# Interfaces.net
KiCad netlist of a schematic drawn in Altium Designer
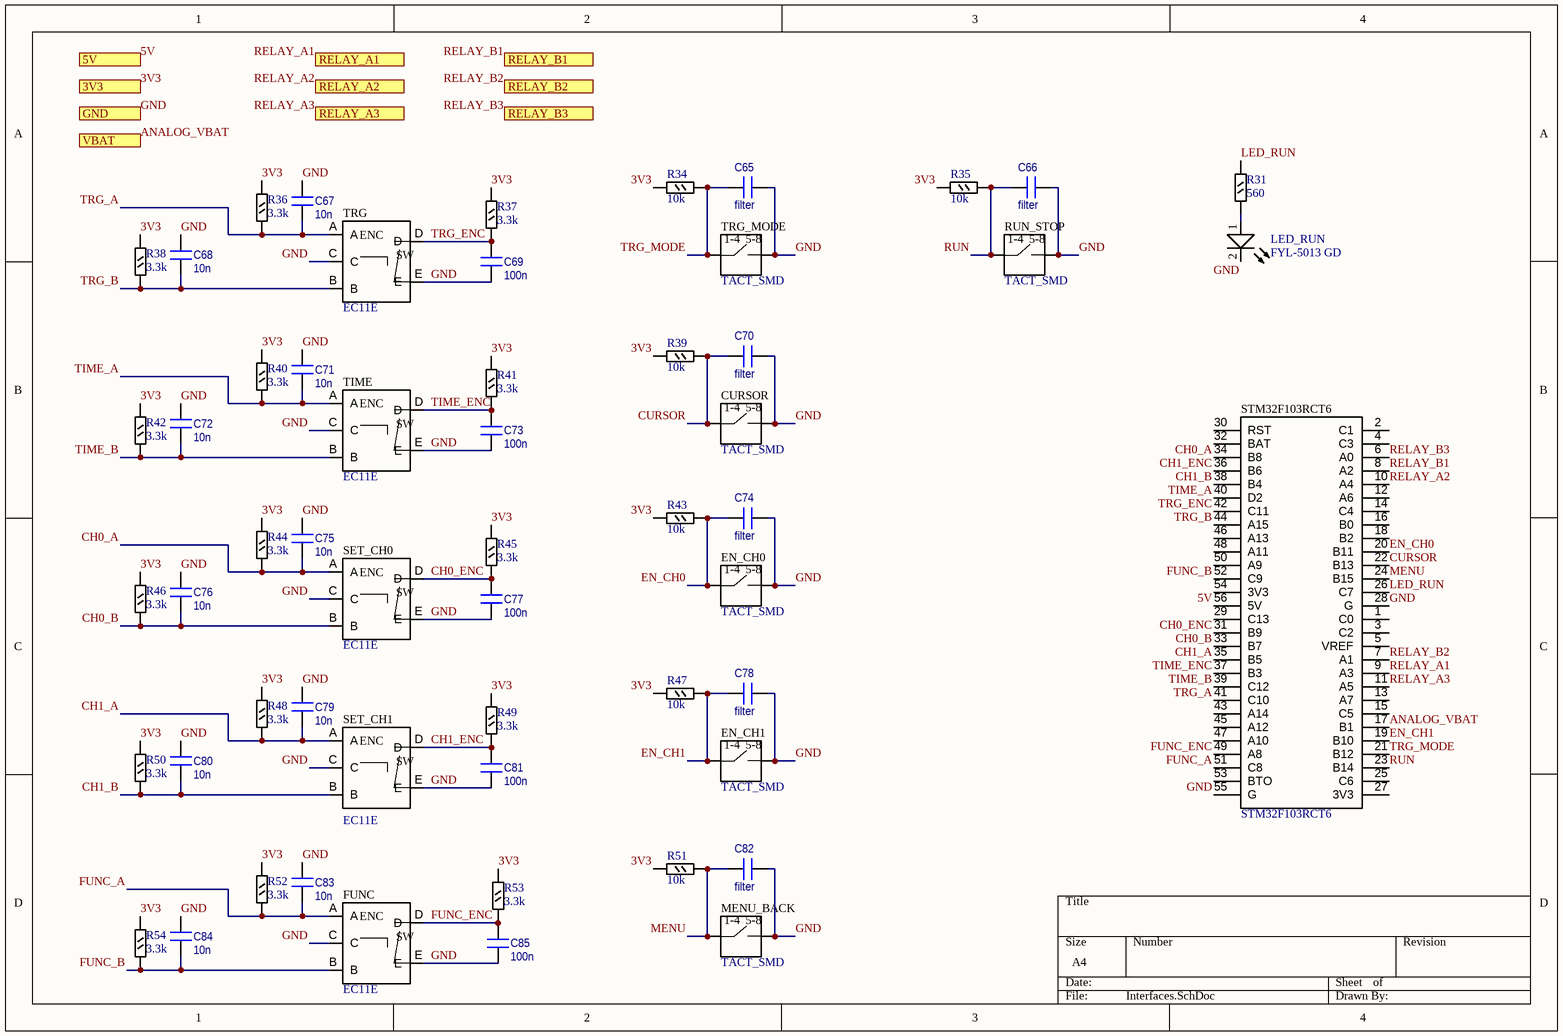
[diagram p0: Interfaces.SchDoc]

(export (version "E")
  (design (tool "Eeschema 10.0.6"))
  (components
    (comp (ref "C65")
      (value "filter")
      (footprint "CAPC2012(0805)N")
      (fields (field (name "PART NUMBER") "CAPC2012(0805)"))
      (libsource (lib "SssAccesDatbase") (part "Capacitor generic"))
    )
    (comp (ref "C66")
      (value "filter")
      (footprint "CAPC2012(0805)N")
      (fields (field (name "PART NUMBER") "CAPC2012(0805)"))
      (libsource (lib "SssAccesDatbase") (part "Capacitor generic"))
    )
    (comp (ref "C67")
      (value "10n")
      (footprint "CAPC2012(0805)N")
      (fields (field (name "PART NUMBER") "CAPC2012(0805)"))
      (libsource (lib "SssAccesDatbase") (part "Capacitor generic"))
    )
    (comp (ref "C68")
      (value "10n")
      (footprint "CAPC2012(0805)N")
      (fields (field (name "PART NUMBER") "CAPC2012(0805)"))
      (libsource (lib "SssAccesDatbase") (part "Capacitor generic"))
    )
    (comp (ref "C69")
      (value "100n")
      (footprint "CAPC2012(0805)N")
      (fields (field (name "PART NUMBER") "CAPC2012(0805)"))
      (libsource (lib "SssAccesDatbase") (part "Capacitor generic"))
    )
    (comp (ref "C70")
      (value "filter")
      (footprint "CAPC2012(0805)N")
      (fields (field (name "PART NUMBER") "CAPC2012(0805)"))
      (libsource (lib "SssAccesDatbase") (part "Capacitor generic"))
    )
    (comp (ref "C71")
      (value "10n")
      (footprint "CAPC2012(0805)N")
      (fields (field (name "PART NUMBER") "CAPC2012(0805)"))
      (libsource (lib "SssAccesDatbase") (part "Capacitor generic"))
    )
    (comp (ref "C72")
      (value "10n")
      (footprint "CAPC2012(0805)N")
      (fields (field (name "PART NUMBER") "CAPC2012(0805)"))
      (libsource (lib "SssAccesDatbase") (part "Capacitor generic"))
    )
    (comp (ref "C73")
      (value "100n")
      (footprint "CAPC2012(0805)N")
      (fields (field (name "PART NUMBER") "CAPC2012(0805)"))
      (libsource (lib "SssAccesDatbase") (part "Capacitor generic"))
    )
    (comp (ref "C74")
      (value "filter")
      (footprint "CAPC2012(0805)N")
      (fields (field (name "PART NUMBER") "CAPC2012(0805)"))
      (libsource (lib "SssAccesDatbase") (part "Capacitor generic"))
    )
    (comp (ref "C75")
      (value "10n")
      (footprint "CAPC2012(0805)N")
      (fields (field (name "PART NUMBER") "CAPC2012(0805)"))
      (libsource (lib "SssAccesDatbase") (part "Capacitor generic"))
    )
    (comp (ref "C76")
      (value "10n")
      (footprint "CAPC2012(0805)N")
      (fields (field (name "PART NUMBER") "CAPC2012(0805)"))
      (libsource (lib "SssAccesDatbase") (part "Capacitor generic"))
    )
    (comp (ref "C77")
      (value "100n")
      (footprint "CAPC2012(0805)N")
      (fields (field (name "PART NUMBER") "CAPC2012(0805)"))
      (libsource (lib "SssAccesDatbase") (part "Capacitor generic"))
    )
    (comp (ref "C78")
      (value "filter")
      (footprint "CAPC2012(0805)N")
      (fields (field (name "PART NUMBER") "CAPC2012(0805)"))
      (libsource (lib "SssAccesDatbase") (part "Capacitor generic"))
    )
    (comp (ref "C79")
      (value "10n")
      (footprint "CAPC2012(0805)N")
      (fields (field (name "PART NUMBER") "CAPC2012(0805)"))
      (libsource (lib "SssAccesDatbase") (part "Capacitor generic"))
    )
    (comp (ref "C80")
      (value "10n")
      (footprint "CAPC2012(0805)N")
      (fields (field (name "PART NUMBER") "CAPC2012(0805)"))
      (libsource (lib "SssAccesDatbase") (part "Capacitor generic"))
    )
    (comp (ref "C81")
      (value "100n")
      (footprint "CAPC2012(0805)N")
      (fields (field (name "PART NUMBER") "CAPC2012(0805)"))
      (libsource (lib "SssAccesDatbase") (part "Capacitor generic"))
    )
    (comp (ref "C82")
      (value "filter")
      (footprint "CAPC2012(0805)N")
      (fields (field (name "PART NUMBER") "CAPC2012(0805)"))
      (libsource (lib "SssAccesDatbase") (part "Capacitor generic"))
    )
    (comp (ref "C83")
      (value "10n")
      (footprint "CAPC2012(0805)N")
      (fields (field (name "PART NUMBER") "CAPC2012(0805)"))
      (libsource (lib "SssAccesDatbase") (part "Capacitor generic"))
    )
    (comp (ref "C84")
      (value "10n")
      (footprint "CAPC2012(0805)N")
      (fields (field (name "PART NUMBER") "CAPC2012(0805)"))
      (libsource (lib "SssAccesDatbase") (part "Capacitor generic"))
    )
    (comp (ref "C85")
      (value "100n")
      (footprint "CAPC2012(0805)N")
      (fields (field (name "PART NUMBER") "CAPC2012(0805)"))
      (libsource (lib "SssAccesDatbase") (part "Capacitor generic"))
    )
    (comp (ref "CURSOR")
      (value "TACT_SMD")
      (footprint "TACT_SMD_ON_DIP8_RAISED")
      (description "Custom raised NO tactile switch; pins 1-4 common, pins 5-8 common")
      (libsource (lib "Oscill") (part "TACT_SMD_ON_DIP8_RAISED"))
    )
    (comp (ref "EN_CH0")
      (value "TACT_SMD")
      (footprint "TACT_SMD_ON_DIP8_RAISED")
      (description "Custom raised NO tactile switch; pins 1-4 common, pins 5-8 common")
      (libsource (lib "Oscill") (part "TACT_SMD_ON_DIP8_RAISED"))
    )
    (comp (ref "EN_CH1")
      (value "TACT_SMD")
      (footprint "TACT_SMD_ON_DIP8_RAISED")
      (description "Custom raised NO tactile switch; pins 1-4 common, pins 5-8 common")
      (libsource (lib "Oscill") (part "TACT_SMD_ON_DIP8_RAISED"))
    )
    (comp (ref "FUNC")
      (value "EC11E")
      (footprint "EC11E_ENCODER_SW")
      (description "Alps Alpine EC11E vertical incremental encoder with one push-on switch")
      (libsource (lib "Oscill") (part "EC11E_ENCODER_SW"))
    )
    (comp (ref "LED_RUN")
      (value "FYL-5013 GD")
      (footprint "LED_3MM_GREEN")
      (libsource (lib "SssAccesDatbase") (part "LED_12"))
    )
    (comp (ref "MENU_BACK")
      (value "TACT_SMD")
      (footprint "TACT_SMD_ON_DIP8_RAISED")
      (description "Custom raised NO tactile switch; pins 1-4 common, pins 5-8 common")
      (libsource (lib "Oscill") (part "TACT_SMD_ON_DIP8_RAISED"))
    )
    (comp (ref "R31")
      (value "560")
      (footprint "RESC2012(0805)N")
      (fields (field (name "PART NUMBER") "RESC2012(0805)"))
      (libsource (lib "SssAccesDatbase") (part "Resistor 0,125W"))
    )
    (comp (ref "R34")
      (value "10k")
      (footprint "RESC2012(0805)N")
      (fields (field (name "PART NUMBER") "RESC2012(0805)"))
      (libsource (lib "") (part "Resistor 0,125W_1"))
    )
    (comp (ref "R35")
      (value "10k")
      (footprint "RESC2012(0805)N")
      (fields (field (name "PART NUMBER") "RESC2012(0805)"))
      (libsource (lib "") (part "Resistor 0,125W_1"))
    )
    (comp (ref "R36")
      (value "3.3k")
      (footprint "RESC2012(0805)N")
      (fields (field (name "PART NUMBER") "RESC2012(0805)"))
      (libsource (lib "SssAccesDatbase") (part "Resistor 0,125W"))
    )
    (comp (ref "R37")
      (value "3.3k")
      (footprint "RESC2012(0805)N")
      (fields (field (name "PART NUMBER") "RESC2012(0805)"))
      (libsource (lib "SssAccesDatbase") (part "Resistor 0,125W"))
    )
    (comp (ref "R38")
      (value "3.3k")
      (footprint "RESC2012(0805)N")
      (fields (field (name "PART NUMBER") "RESC2012(0805)"))
      (libsource (lib "SssAccesDatbase") (part "Resistor 0,125W"))
    )
    (comp (ref "R39")
      (value "10k")
      (footprint "RESC2012(0805)N")
      (fields (field (name "PART NUMBER") "RESC2012(0805)"))
      (libsource (lib "") (part "Resistor 0,125W_1"))
    )
    (comp (ref "R40")
      (value "3.3k")
      (footprint "RESC2012(0805)N")
      (fields (field (name "PART NUMBER") "RESC2012(0805)"))
      (libsource (lib "SssAccesDatbase") (part "Resistor 0,125W"))
    )
    (comp (ref "R41")
      (value "3.3k")
      (footprint "RESC2012(0805)N")
      (fields (field (name "PART NUMBER") "RESC2012(0805)"))
      (libsource (lib "SssAccesDatbase") (part "Resistor 0,125W"))
    )
    (comp (ref "R42")
      (value "3.3k")
      (footprint "RESC2012(0805)N")
      (fields (field (name "PART NUMBER") "RESC2012(0805)"))
      (libsource (lib "SssAccesDatbase") (part "Resistor 0,125W"))
    )
    (comp (ref "R43")
      (value "10k")
      (footprint "RESC2012(0805)N")
      (fields (field (name "PART NUMBER") "RESC2012(0805)"))
      (libsource (lib "") (part "Resistor 0,125W_1"))
    )
    (comp (ref "R44")
      (value "3.3k")
      (footprint "RESC2012(0805)N")
      (fields (field (name "PART NUMBER") "RESC2012(0805)"))
      (libsource (lib "SssAccesDatbase") (part "Resistor 0,125W"))
    )
    (comp (ref "R45")
      (value "3.3k")
      (footprint "RESC2012(0805)N")
      (fields (field (name "PART NUMBER") "RESC2012(0805)"))
      (libsource (lib "SssAccesDatbase") (part "Resistor 0,125W"))
    )
    (comp (ref "R46")
      (value "3.3k")
      (footprint "RESC2012(0805)N")
      (fields (field (name "PART NUMBER") "RESC2012(0805)"))
      (libsource (lib "SssAccesDatbase") (part "Resistor 0,125W"))
    )
    (comp (ref "R47")
      (value "10k")
      (footprint "RESC2012(0805)N")
      (fields (field (name "PART NUMBER") "RESC2012(0805)"))
      (libsource (lib "") (part "Resistor 0,125W_1"))
    )
    (comp (ref "R48")
      (value "3.3k")
      (footprint "RESC2012(0805)N")
      (fields (field (name "PART NUMBER") "RESC2012(0805)"))
      (libsource (lib "SssAccesDatbase") (part "Resistor 0,125W"))
    )
    (comp (ref "R49")
      (value "3.3k")
      (footprint "RESC2012(0805)N")
      (fields (field (name "PART NUMBER") "RESC2012(0805)"))
      (libsource (lib "SssAccesDatbase") (part "Resistor 0,125W"))
    )
    (comp (ref "R50")
      (value "3.3k")
      (footprint "RESC2012(0805)N")
      (fields (field (name "PART NUMBER") "RESC2012(0805)"))
      (libsource (lib "SssAccesDatbase") (part "Resistor 0,125W"))
    )
    (comp (ref "R51")
      (value "10k")
      (footprint "RESC2012(0805)N")
      (fields (field (name "PART NUMBER") "RESC2012(0805)"))
      (libsource (lib "") (part "Resistor 0,125W_1"))
    )
    (comp (ref "R52")
      (value "3.3k")
      (footprint "RESC2012(0805)N")
      (fields (field (name "PART NUMBER") "RESC2012(0805)"))
      (libsource (lib "SssAccesDatbase") (part "Resistor 0,125W"))
    )
    (comp (ref "R53")
      (value "3.3k")
      (footprint "RESC2012(0805)N")
      (fields (field (name "PART NUMBER") "RESC2012(0805)"))
      (libsource (lib "SssAccesDatbase") (part "Resistor 0,125W"))
    )
    (comp (ref "R54")
      (value "3.3k")
      (footprint "RESC2012(0805)N")
      (fields (field (name "PART NUMBER") "RESC2012(0805)"))
      (libsource (lib "SssAccesDatbase") (part "Resistor 0,125W"))
    )
    (comp (ref "RUN_STOP")
      (value "TACT_SMD")
      (footprint "TACT_SMD_ON_DIP8_RAISED")
      (description "Custom raised NO tactile switch; pins 1-4 common, pins 5-8 common")
      (libsource (lib "Oscill") (part "TACT_SMD_ON_DIP8_RAISED"))
    )
    (comp (ref "SET_CH0")
      (value "EC11E")
      (footprint "EC11E_ENCODER_SW")
      (description "Alps Alpine EC11E vertical incremental encoder with one push-on switch")
      (libsource (lib "Oscill") (part "EC11E_ENCODER_SW"))
    )
    (comp (ref "SET_CH1")
      (value "EC11E")
      (footprint "EC11E_ENCODER_SW")
      (description "Alps Alpine EC11E vertical incremental encoder with one push-on switch")
      (libsource (lib "Oscill") (part "EC11E_ENCODER_SW"))
    )
    (comp (ref "STM32F103RCT6")
      (value "STM32F103RCT6")
      (footprint "Oscill:STM32F103RCT6_MODULE_PBD_2X14")
      (description "STM32F103RCT6 core board, 56 pins, two PBD 2x14 sockets")
      (libsource (lib "Oscill") (part "STM32F103RCT6_MODULE_PBD_2X14"))
    )
    (comp (ref "TIME")
      (value "EC11E")
      (footprint "EC11E_ENCODER_SW")
      (description "Alps Alpine EC11E vertical incremental encoder with one push-on switch")
      (libsource (lib "Oscill") (part "EC11E_ENCODER_SW"))
    )
    (comp (ref "TRG")
      (value "EC11E")
      (footprint "EC11E_ENCODER_SW")
      (description "Alps Alpine EC11E vertical incremental encoder with one push-on switch")
      (libsource (lib "Oscill") (part "EC11E_ENCODER_SW"))
    )
    (comp (ref "TRG_MODE")
      (value "TACT_SMD")
      (footprint "TACT_SMD_ON_DIP8_RAISED")
      (description "Custom raised NO tactile switch; pins 1-4 common, pins 5-8 common")
      (libsource (lib "Oscill") (part "TACT_SMD_ON_DIP8_RAISED"))
    )
  )
  (nets
    (net (code "1") (name "/3V3") (class "Default")
      (node (ref "R34") (pin "2") (pinfunction "2_2") (pintype "passive"))
      (node (ref "R35") (pin "2") (pinfunction "2_2") (pintype "passive"))
      (node (ref "R36") (pin "2") (pinfunction "2_2") (pintype "passive"))
      (node (ref "R37") (pin "2") (pinfunction "2_2") (pintype "passive"))
      (node (ref "R38") (pin "2") (pinfunction "2_2") (pintype "passive"))
      (node (ref "R39") (pin "2") (pinfunction "2_2") (pintype "passive"))
      (node (ref "R40") (pin "2") (pinfunction "2_2") (pintype "passive"))
      (node (ref "R41") (pin "2") (pinfunction "2_2") (pintype "passive"))
      (node (ref "R42") (pin "2") (pinfunction "2_2") (pintype "passive"))
      (node (ref "R43") (pin "2") (pinfunction "2_2") (pintype "passive"))
      (node (ref "R44") (pin "2") (pinfunction "2_2") (pintype "passive"))
      (node (ref "R45") (pin "2") (pinfunction "2_2") (pintype "passive"))
      (node (ref "R46") (pin "2") (pinfunction "2_2") (pintype "passive"))
      (node (ref "R47") (pin "2") (pinfunction "2_2") (pintype "passive"))
      (node (ref "R48") (pin "2") (pinfunction "2_2") (pintype "passive"))
      (node (ref "R49") (pin "2") (pinfunction "2_2") (pintype "passive"))
      (node (ref "R50") (pin "2") (pinfunction "2_2") (pintype "passive"))
      (node (ref "R51") (pin "2") (pinfunction "2_2") (pintype "passive"))
      (node (ref "R52") (pin "2") (pinfunction "2_2") (pintype "passive"))
      (node (ref "R53") (pin "2") (pinfunction "2_2") (pintype "passive"))
      (node (ref "R54") (pin "2") (pinfunction "2_2") (pintype "passive"))
    )
    (net (code "2") (name "/5V") (class "Default")
      (node (ref "STM32F103RCT6") (pin "56") (pinfunction "5V_56") (pintype "passive"))
    )
    (net (code "3") (name "/ANALOG_VBAT") (class "Default")
      (node (ref "STM32F103RCT6") (pin "17") (pinfunction "B1_17") (pintype "passive"))
    )
    (net (code "4") (name "/CH0_A") (class "Default")
      (node (ref "C75") (pin "1") (pinfunction "1_1") (pintype "passive"))
      (node (ref "R44") (pin "1") (pinfunction "1_1") (pintype "passive"))
      (node (ref "SET_CH0") (pin "A") (pinfunction "A_A") (pintype "passive"))
      (node (ref "STM32F103RCT6") (pin "34") (pinfunction "B8_34") (pintype "passive"))
    )
    (net (code "5") (name "/CH0_B") (class "Default")
      (node (ref "C76") (pin "1") (pinfunction "1_1") (pintype "passive"))
      (node (ref "R46") (pin "1") (pinfunction "1_1") (pintype "passive"))
      (node (ref "SET_CH0") (pin "B") (pinfunction "B_B") (pintype "passive"))
      (node (ref "STM32F103RCT6") (pin "33") (pinfunction "B7_33") (pintype "passive"))
    )
    (net (code "6") (name "/CH0_ENC") (class "Default")
      (node (ref "C77") (pin "2") (pinfunction "2_2") (pintype "passive"))
      (node (ref "R45") (pin "1") (pinfunction "1_1") (pintype "passive"))
      (node (ref "SET_CH0") (pin "D") (pinfunction "D_D") (pintype "passive"))
      (node (ref "STM32F103RCT6") (pin "31") (pinfunction "B9_31") (pintype "passive"))
    )
    (net (code "7") (name "/CH1_A") (class "Default")
      (node (ref "C79") (pin "1") (pinfunction "1_1") (pintype "passive"))
      (node (ref "R48") (pin "1") (pinfunction "1_1") (pintype "passive"))
      (node (ref "SET_CH1") (pin "A") (pinfunction "A_A") (pintype "passive"))
      (node (ref "STM32F103RCT6") (pin "35") (pinfunction "B5_35") (pintype "passive"))
    )
    (net (code "8") (name "/CH1_B") (class "Default")
      (node (ref "C80") (pin "1") (pinfunction "1_1") (pintype "passive"))
      (node (ref "R50") (pin "1") (pinfunction "1_1") (pintype "passive"))
      (node (ref "SET_CH1") (pin "B") (pinfunction "B_B") (pintype "passive"))
      (node (ref "STM32F103RCT6") (pin "38") (pinfunction "B4_38") (pintype "passive"))
    )
    (net (code "9") (name "/CH1_ENC") (class "Default")
      (node (ref "C81") (pin "2") (pinfunction "2_2") (pintype "passive"))
      (node (ref "R49") (pin "1") (pinfunction "1_1") (pintype "passive"))
      (node (ref "SET_CH1") (pin "D") (pinfunction "D_D") (pintype "passive"))
      (node (ref "STM32F103RCT6") (pin "36") (pinfunction "B6_36") (pintype "passive"))
    )
    (net (code "10") (name "/CURSOR") (class "Default")
      (node (ref "C70") (pin "1") (pinfunction "1_1") (pintype "passive"))
      (node (ref "CURSOR") (pin "1") (pinfunction "A_1") (pintype "passive"))
      (node (ref "CURSOR") (pin "2") (pinfunction "A_2") (pintype "passive"))
      (node (ref "CURSOR") (pin "3") (pinfunction "A_3") (pintype "passive"))
      (node (ref "CURSOR") (pin "4") (pinfunction "A_4") (pintype "passive"))
      (node (ref "R39") (pin "1") (pinfunction "1_1") (pintype "passive"))
      (node (ref "STM32F103RCT6") (pin "22") (pinfunction "B13_22") (pintype "passive"))
    )
    (net (code "11") (name "/EN_CH0") (class "Default")
      (node (ref "C74") (pin "1") (pinfunction "1_1") (pintype "passive"))
      (node (ref "EN_CH0") (pin "1") (pinfunction "A_1") (pintype "passive"))
      (node (ref "EN_CH0") (pin "2") (pinfunction "A_2") (pintype "passive"))
      (node (ref "EN_CH0") (pin "3") (pinfunction "A_3") (pintype "passive"))
      (node (ref "EN_CH0") (pin "4") (pinfunction "A_4") (pintype "passive"))
      (node (ref "R43") (pin "1") (pinfunction "1_1") (pintype "passive"))
      (node (ref "STM32F103RCT6") (pin "20") (pinfunction "B11_20") (pintype "passive"))
    )
    (net (code "12") (name "/EN_CH1") (class "Default")
      (node (ref "C78") (pin "1") (pinfunction "1_1") (pintype "passive"))
      (node (ref "EN_CH1") (pin "1") (pinfunction "A_1") (pintype "passive"))
      (node (ref "EN_CH1") (pin "2") (pinfunction "A_2") (pintype "passive"))
      (node (ref "EN_CH1") (pin "3") (pinfunction "A_3") (pintype "passive"))
      (node (ref "EN_CH1") (pin "4") (pinfunction "A_4") (pintype "passive"))
      (node (ref "R47") (pin "1") (pinfunction "1_1") (pintype "passive"))
      (node (ref "STM32F103RCT6") (pin "19") (pinfunction "B10_19") (pintype "passive"))
    )
    (net (code "13") (name "/FUNC_A") (class "Default")
      (node (ref "C83") (pin "1") (pinfunction "1_1") (pintype "passive"))
      (node (ref "FUNC") (pin "A") (pinfunction "A_A") (pintype "passive"))
      (node (ref "R52") (pin "1") (pinfunction "1_1") (pintype "passive"))
      (node (ref "STM32F103RCT6") (pin "51") (pinfunction "C8_51") (pintype "passive"))
    )
    (net (code "14") (name "/FUNC_B") (class "Default")
      (node (ref "C84") (pin "1") (pinfunction "1_1") (pintype "passive"))
      (node (ref "FUNC") (pin "B") (pinfunction "B_B") (pintype "passive"))
      (node (ref "R54") (pin "1") (pinfunction "1_1") (pintype "passive"))
      (node (ref "STM32F103RCT6") (pin "52") (pinfunction "C9_52") (pintype "passive"))
    )
    (net (code "15") (name "/FUNC_ENC") (class "Default")
      (node (ref "C85") (pin "2") (pinfunction "2_2") (pintype "passive"))
      (node (ref "FUNC") (pin "D") (pinfunction "D_D") (pintype "passive"))
      (node (ref "R53") (pin "1") (pinfunction "1_1") (pintype "passive"))
      (node (ref "STM32F103RCT6") (pin "49") (pinfunction "A8_49") (pintype "passive"))
    )
    (net (code "16") (name "/GND") (class "Default")
      (node (ref "C65") (pin "2") (pinfunction "2_2") (pintype "passive"))
      (node (ref "C66") (pin "2") (pinfunction "2_2") (pintype "passive"))
      (node (ref "C67") (pin "2") (pinfunction "2_2") (pintype "passive"))
      (node (ref "C68") (pin "2") (pinfunction "2_2") (pintype "passive"))
      (node (ref "C69") (pin "1") (pinfunction "1_1") (pintype "passive"))
      (node (ref "C70") (pin "2") (pinfunction "2_2") (pintype "passive"))
      (node (ref "C71") (pin "2") (pinfunction "2_2") (pintype "passive"))
      (node (ref "C72") (pin "2") (pinfunction "2_2") (pintype "passive"))
      (node (ref "C73") (pin "1") (pinfunction "1_1") (pintype "passive"))
      (node (ref "C74") (pin "2") (pinfunction "2_2") (pintype "passive"))
      (node (ref "C75") (pin "2") (pinfunction "2_2") (pintype "passive"))
      (node (ref "C76") (pin "2") (pinfunction "2_2") (pintype "passive"))
      (node (ref "C77") (pin "1") (pinfunction "1_1") (pintype "passive"))
      (node (ref "C78") (pin "2") (pinfunction "2_2") (pintype "passive"))
      (node (ref "C79") (pin "2") (pinfunction "2_2") (pintype "passive"))
      (node (ref "C80") (pin "2") (pinfunction "2_2") (pintype "passive"))
      (node (ref "C81") (pin "1") (pinfunction "1_1") (pintype "passive"))
      (node (ref "C82") (pin "2") (pinfunction "2_2") (pintype "passive"))
      (node (ref "C83") (pin "2") (pinfunction "2_2") (pintype "passive"))
      (node (ref "C84") (pin "2") (pinfunction "2_2") (pintype "passive"))
      (node (ref "C85") (pin "1") (pinfunction "1_1") (pintype "passive"))
      (node (ref "CURSOR") (pin "5") (pinfunction "B_5") (pintype "passive"))
      (node (ref "CURSOR") (pin "6") (pinfunction "B_6") (pintype "passive"))
      (node (ref "CURSOR") (pin "7") (pinfunction "B_7") (pintype "passive"))
      (node (ref "CURSOR") (pin "8") (pinfunction "B_8") (pintype "passive"))
      (node (ref "EN_CH0") (pin "5") (pinfunction "B_5") (pintype "passive"))
      (node (ref "EN_CH0") (pin "6") (pinfunction "B_6") (pintype "passive"))
      (node (ref "EN_CH0") (pin "7") (pinfunction "B_7") (pintype "passive"))
      (node (ref "EN_CH0") (pin "8") (pinfunction "B_8") (pintype "passive"))
      (node (ref "EN_CH1") (pin "5") (pinfunction "B_5") (pintype "passive"))
      (node (ref "EN_CH1") (pin "6") (pinfunction "B_6") (pintype "passive"))
      (node (ref "EN_CH1") (pin "7") (pinfunction "B_7") (pintype "passive"))
      (node (ref "EN_CH1") (pin "8") (pinfunction "B_8") (pintype "passive"))
      (node (ref "FUNC") (pin "C") (pinfunction "C_C") (pintype "passive"))
      (node (ref "FUNC") (pin "E") (pinfunction "E_E") (pintype "passive"))
      (node (ref "LED_RUN") (pin "2") (pinfunction "K_2") (pintype "passive"))
      (node (ref "MENU_BACK") (pin "5") (pinfunction "B_5") (pintype "passive"))
      (node (ref "MENU_BACK") (pin "6") (pinfunction "B_6") (pintype "passive"))
      (node (ref "MENU_BACK") (pin "7") (pinfunction "B_7") (pintype "passive"))
      (node (ref "MENU_BACK") (pin "8") (pinfunction "B_8") (pintype "passive"))
      (node (ref "RUN_STOP") (pin "5") (pinfunction "B_5") (pintype "passive"))
      (node (ref "RUN_STOP") (pin "6") (pinfunction "B_6") (pintype "passive"))
      (node (ref "RUN_STOP") (pin "7") (pinfunction "B_7") (pintype "passive"))
      (node (ref "RUN_STOP") (pin "8") (pinfunction "B_8") (pintype "passive"))
      (node (ref "SET_CH0") (pin "C") (pinfunction "C_C") (pintype "passive"))
      (node (ref "SET_CH0") (pin "E") (pinfunction "E_E") (pintype "passive"))
      (node (ref "SET_CH1") (pin "C") (pinfunction "C_C") (pintype "passive"))
      (node (ref "SET_CH1") (pin "E") (pinfunction "E_E") (pintype "passive"))
      (node (ref "STM32F103RCT6") (pin "28") (pinfunction "G_28") (pintype "passive"))
      (node (ref "STM32F103RCT6") (pin "55") (pinfunction "G_55") (pintype "passive"))
      (node (ref "TIME") (pin "C") (pinfunction "C_C") (pintype "passive"))
      (node (ref "TIME") (pin "E") (pinfunction "E_E") (pintype "passive"))
      (node (ref "TRG") (pin "C") (pinfunction "C_C") (pintype "passive"))
      (node (ref "TRG") (pin "E") (pinfunction "E_E") (pintype "passive"))
      (node (ref "TRG_MODE") (pin "5") (pinfunction "B_5") (pintype "passive"))
      (node (ref "TRG_MODE") (pin "6") (pinfunction "B_6") (pintype "passive"))
      (node (ref "TRG_MODE") (pin "7") (pinfunction "B_7") (pintype "passive"))
      (node (ref "TRG_MODE") (pin "8") (pinfunction "B_8") (pintype "passive"))
    )
    (net (code "17") (name "/LED_RUN") (class "Default")
      (node (ref "R31") (pin "2") (pinfunction "2_2") (pintype "passive"))
      (node (ref "STM32F103RCT6") (pin "26") (pinfunction "C7_26") (pintype "passive"))
    )
    (net (code "18") (name "/MENU") (class "Default")
      (node (ref "C82") (pin "1") (pinfunction "1_1") (pintype "passive"))
      (node (ref "MENU_BACK") (pin "1") (pinfunction "A_1") (pintype "passive"))
      (node (ref "MENU_BACK") (pin "2") (pinfunction "A_2") (pintype "passive"))
      (node (ref "MENU_BACK") (pin "3") (pinfunction "A_3") (pintype "passive"))
      (node (ref "MENU_BACK") (pin "4") (pinfunction "A_4") (pintype "passive"))
      (node (ref "R51") (pin "1") (pinfunction "1_1") (pintype "passive"))
      (node (ref "STM32F103RCT6") (pin "24") (pinfunction "B15_24") (pintype "passive"))
    )
    (net (code "19") (name "/RELAY_A1") (class "Default")
      (node (ref "STM32F103RCT6") (pin "9") (pinfunction "A3_9") (pintype "passive"))
    )
    (net (code "20") (name "/RELAY_A2") (class "Default")
      (node (ref "STM32F103RCT6") (pin "10") (pinfunction "A4_10") (pintype "passive"))
    )
    (net (code "21") (name "/RELAY_A3") (class "Default")
      (node (ref "STM32F103RCT6") (pin "11") (pinfunction "A5_11") (pintype "passive"))
    )
    (net (code "22") (name "/RELAY_B1") (class "Default")
      (node (ref "STM32F103RCT6") (pin "8") (pinfunction "A2_8") (pintype "passive"))
    )
    (net (code "23") (name "/RELAY_B2") (class "Default")
      (node (ref "STM32F103RCT6") (pin "7") (pinfunction "A1_7") (pintype "passive"))
    )
    (net (code "24") (name "/RELAY_B3") (class "Default")
      (node (ref "STM32F103RCT6") (pin "6") (pinfunction "A0_6") (pintype "passive"))
    )
    (net (code "25") (name "/RUN") (class "Default")
      (node (ref "C66") (pin "1") (pinfunction "1_1") (pintype "passive"))
      (node (ref "R35") (pin "1") (pinfunction "1_1") (pintype "passive"))
      (node (ref "RUN_STOP") (pin "1") (pinfunction "A_1") (pintype "passive"))
      (node (ref "RUN_STOP") (pin "2") (pinfunction "A_2") (pintype "passive"))
      (node (ref "RUN_STOP") (pin "3") (pinfunction "A_3") (pintype "passive"))
      (node (ref "RUN_STOP") (pin "4") (pinfunction "A_4") (pintype "passive"))
      (node (ref "STM32F103RCT6") (pin "23") (pinfunction "B14_23") (pintype "passive"))
    )
    (net (code "26") (name "/TIME_A") (class "Default")
      (node (ref "C71") (pin "1") (pinfunction "1_1") (pintype "passive"))
      (node (ref "R40") (pin "1") (pinfunction "1_1") (pintype "passive"))
      (node (ref "STM32F103RCT6") (pin "40") (pinfunction "D2_40") (pintype "passive"))
      (node (ref "TIME") (pin "A") (pinfunction "A_A") (pintype "passive"))
    )
    (net (code "27") (name "/TIME_B") (class "Default")
      (node (ref "C72") (pin "1") (pinfunction "1_1") (pintype "passive"))
      (node (ref "R42") (pin "1") (pinfunction "1_1") (pintype "passive"))
      (node (ref "STM32F103RCT6") (pin "39") (pinfunction "C12_39") (pintype "passive"))
      (node (ref "TIME") (pin "B") (pinfunction "B_B") (pintype "passive"))
    )
    (net (code "28") (name "/TIME_ENC") (class "Default")
      (node (ref "C73") (pin "2") (pinfunction "2_2") (pintype "passive"))
      (node (ref "R41") (pin "1") (pinfunction "1_1") (pintype "passive"))
      (node (ref "STM32F103RCT6") (pin "37") (pinfunction "B3_37") (pintype "passive"))
      (node (ref "TIME") (pin "D") (pinfunction "D_D") (pintype "passive"))
    )
    (net (code "29") (name "/TRG_A") (class "Default")
      (node (ref "C67") (pin "1") (pinfunction "1_1") (pintype "passive"))
      (node (ref "R36") (pin "1") (pinfunction "1_1") (pintype "passive"))
      (node (ref "STM32F103RCT6") (pin "41") (pinfunction "C10_41") (pintype "passive"))
      (node (ref "TRG") (pin "A") (pinfunction "A_A") (pintype "passive"))
    )
    (net (code "30") (name "/TRG_B") (class "Default")
      (node (ref "C68") (pin "1") (pinfunction "1_1") (pintype "passive"))
      (node (ref "R38") (pin "1") (pinfunction "1_1") (pintype "passive"))
      (node (ref "STM32F103RCT6") (pin "44") (pinfunction "A15_44") (pintype "passive"))
      (node (ref "TRG") (pin "B") (pinfunction "B_B") (pintype "passive"))
    )
    (net (code "31") (name "/TRG_ENC") (class "Default")
      (node (ref "C69") (pin "2") (pinfunction "2_2") (pintype "passive"))
      (node (ref "R37") (pin "1") (pinfunction "1_1") (pintype "passive"))
      (node (ref "STM32F103RCT6") (pin "42") (pinfunction "C11_42") (pintype "passive"))
      (node (ref "TRG") (pin "D") (pinfunction "D_D") (pintype "passive"))
    )
    (net (code "32") (name "/TRG_MODE") (class "Default")
      (node (ref "C65") (pin "1") (pinfunction "1_1") (pintype "passive"))
      (node (ref "R34") (pin "1") (pinfunction "1_1") (pintype "passive"))
      (node (ref "STM32F103RCT6") (pin "21") (pinfunction "B12_21") (pintype "passive"))
      (node (ref "TRG_MODE") (pin "1") (pinfunction "A_1") (pintype "passive"))
      (node (ref "TRG_MODE") (pin "2") (pinfunction "A_2") (pintype "passive"))
      (node (ref "TRG_MODE") (pin "3") (pinfunction "A_3") (pintype "passive"))
      (node (ref "TRG_MODE") (pin "4") (pinfunction "A_4") (pintype "passive"))
    )
    (net (code "33") (name "Net-(LED_RUN-A)") (class "Default")
      (node (ref "LED_RUN") (pin "1") (pinfunction "A_1") (pintype "passive"))
      (node (ref "R31") (pin "1") (pinfunction "1_1") (pintype "passive"))
    )
    (net (code "34") (name "unconnected-(STM32F103RCT6-3V3-Pad27)") (class "Default")
      (node (ref "STM32F103RCT6") (pin "27") (pinfunction "3V3_27") (pintype "passive"))
    )
    (net (code "35") (name "unconnected-(STM32F103RCT6-3V3-Pad54)") (class "Default")
      (node (ref "STM32F103RCT6") (pin "54") (pinfunction "3V3_54") (pintype "passive"))
    )
    (net (code "36") (name "unconnected-(STM32F103RCT6-A6-Pad12)") (class "Default")
      (node (ref "STM32F103RCT6") (pin "12") (pinfunction "A6_12") (pintype "passive"))
    )
    (net (code "37") (name "unconnected-(STM32F103RCT6-A7-Pad13)") (class "Default")
      (node (ref "STM32F103RCT6") (pin "13") (pinfunction "A7_13") (pintype "passive"))
    )
    (net (code "38") (name "unconnected-(STM32F103RCT6-A9-Pad50)") (class "Default")
      (node (ref "STM32F103RCT6") (pin "50") (pinfunction "A9_50") (pintype "passive"))
    )
    (net (code "39") (name "unconnected-(STM32F103RCT6-A10-Pad47)") (class "Default")
      (node (ref "STM32F103RCT6") (pin "47") (pinfunction "A10_47") (pintype "passive"))
    )
    (net (code "40") (name "unconnected-(STM32F103RCT6-A11-Pad48)") (class "Default")
      (node (ref "STM32F103RCT6") (pin "48") (pinfunction "A11_48") (pintype "passive"))
    )
    (net (code "41") (name "unconnected-(STM32F103RCT6-A12-Pad45)") (class "Default")
      (node (ref "STM32F103RCT6") (pin "45") (pinfunction "A12_45") (pintype "passive"))
    )
    (net (code "42") (name "unconnected-(STM32F103RCT6-A13-Pad46)") (class "Default")
      (node (ref "STM32F103RCT6") (pin "46") (pinfunction "A13_46") (pintype "passive"))
    )
    (net (code "43") (name "unconnected-(STM32F103RCT6-A14-Pad43)") (class "Default")
      (node (ref "STM32F103RCT6") (pin "43") (pinfunction "A14_43") (pintype "passive"))
    )
    (net (code "44") (name "unconnected-(STM32F103RCT6-B0-Pad16)") (class "Default")
      (node (ref "STM32F103RCT6") (pin "16") (pinfunction "B0_16") (pintype "passive"))
    )
    (net (code "45") (name "unconnected-(STM32F103RCT6-B2-Pad18)") (class "Default")
      (node (ref "STM32F103RCT6") (pin "18") (pinfunction "B2_18") (pintype "passive"))
    )
    (net (code "46") (name "unconnected-(STM32F103RCT6-BAT-Pad32)") (class "Default")
      (node (ref "STM32F103RCT6") (pin "32") (pinfunction "BAT_32") (pintype "passive"))
    )
    (net (code "47") (name "unconnected-(STM32F103RCT6-BTO-Pad53)") (class "Default")
      (node (ref "STM32F103RCT6") (pin "53") (pinfunction "BTO_53") (pintype "passive"))
    )
    (net (code "48") (name "unconnected-(STM32F103RCT6-C0-Pad1)") (class "Default")
      (node (ref "STM32F103RCT6") (pin "1") (pinfunction "C0_1") (pintype "passive"))
    )
    (net (code "49") (name "unconnected-(STM32F103RCT6-C1-Pad2)") (class "Default")
      (node (ref "STM32F103RCT6") (pin "2") (pinfunction "C1_2") (pintype "passive"))
    )
    (net (code "50") (name "unconnected-(STM32F103RCT6-C2-Pad3)") (class "Default")
      (node (ref "STM32F103RCT6") (pin "3") (pinfunction "C2_3") (pintype "passive"))
    )
    (net (code "51") (name "unconnected-(STM32F103RCT6-C3-Pad4)") (class "Default")
      (node (ref "STM32F103RCT6") (pin "4") (pinfunction "C3_4") (pintype "passive"))
    )
    (net (code "52") (name "unconnected-(STM32F103RCT6-C4-Pad14)") (class "Default")
      (node (ref "STM32F103RCT6") (pin "14") (pinfunction "C4_14") (pintype "passive"))
    )
    (net (code "53") (name "unconnected-(STM32F103RCT6-C5-Pad15)") (class "Default")
      (node (ref "STM32F103RCT6") (pin "15") (pinfunction "C5_15") (pintype "passive"))
    )
    (net (code "54") (name "unconnected-(STM32F103RCT6-C6-Pad25)") (class "Default")
      (node (ref "STM32F103RCT6") (pin "25") (pinfunction "C6_25") (pintype "passive"))
    )
    (net (code "55") (name "unconnected-(STM32F103RCT6-C13-Pad29)") (class "Default")
      (node (ref "STM32F103RCT6") (pin "29") (pinfunction "C13_29") (pintype "passive"))
    )
    (net (code "56") (name "unconnected-(STM32F103RCT6-RST-Pad30)") (class "Default")
      (node (ref "STM32F103RCT6") (pin "30") (pinfunction "RST_30") (pintype "passive"))
    )
    (net (code "57") (name "unconnected-(STM32F103RCT6-VREF-Pad5)") (class "Default")
      (node (ref "STM32F103RCT6") (pin "5") (pinfunction "VREF_5") (pintype "passive"))
    )
  )
)
